# dmi.net
KiCad netlist of a schematic drawn in EAGLE
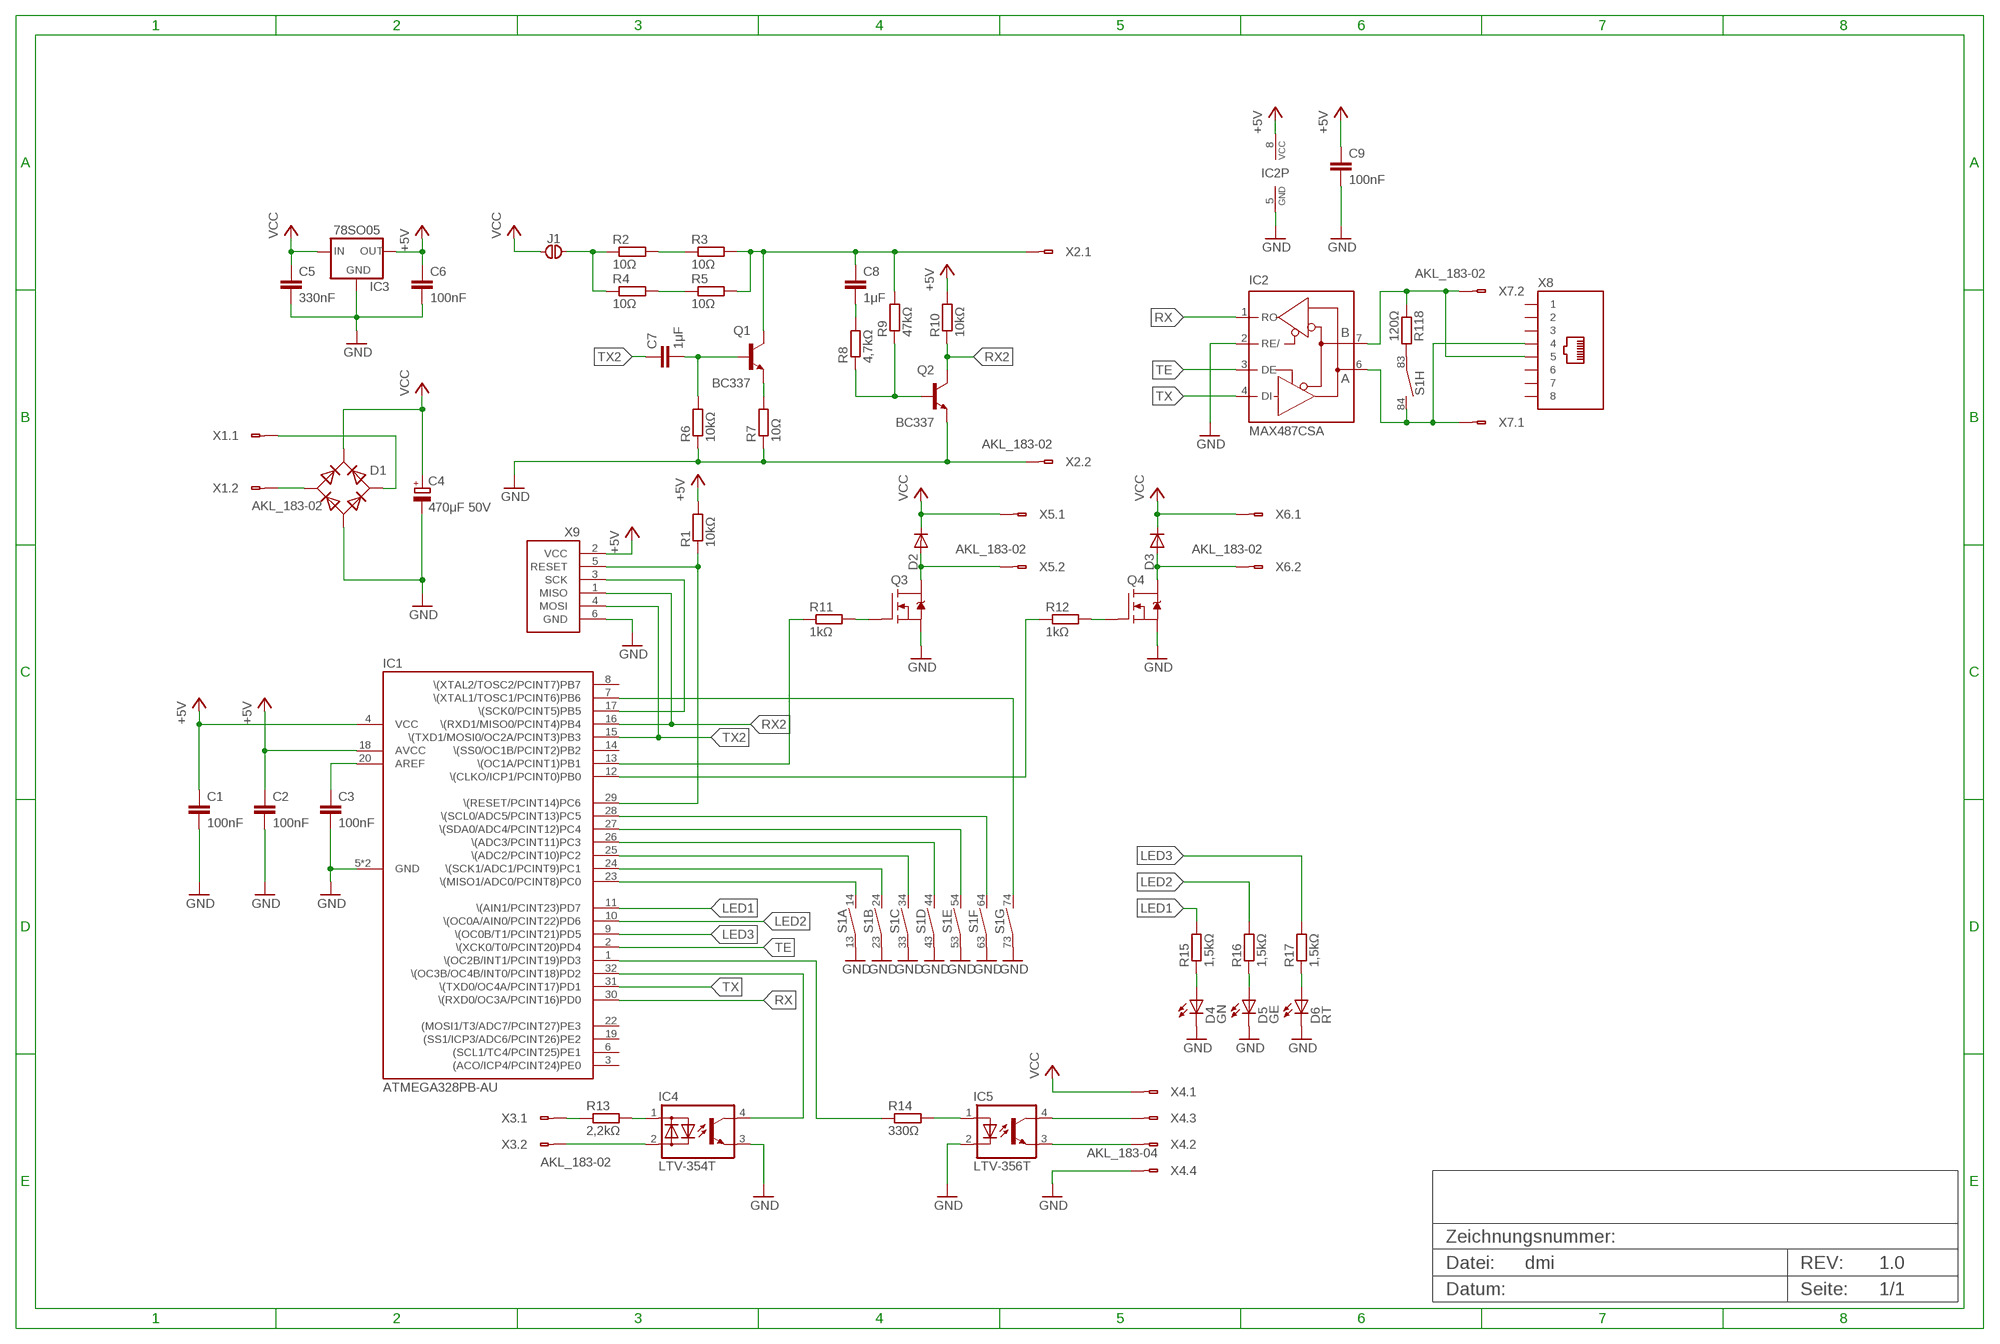
[diagram p0: schematic, sheet 1]

(export (version "E")
  (design (tool "Eeschema 10.0.6"))
  (components
    (comp (ref "C1")
      (value "100nF")
      (footprint "eagle-import:CHIP_0603")
      (libsource (lib "eagle-import") (part "C_0603"))
    )
    (comp (ref "C2")
      (value "100nF")
      (footprint "eagle-import:CHIP_0603")
      (libsource (lib "eagle-import") (part "C_0603"))
    )
    (comp (ref "C3")
      (value "100nF")
      (footprint "eagle-import:CHIP_0603")
      (libsource (lib "eagle-import") (part "C_0603"))
    )
    (comp (ref "C4")
      (value "470μF 50V")
      (footprint "eagle-import:E5-13")
      (libsource (lib "eagle-import") (part "C_EL_E5-13"))
    )
    (comp (ref "C5")
      (value "330nF")
      (footprint "eagle-import:CHIP_0805")
      (libsource (lib "eagle-import") (part "C_0805"))
    )
    (comp (ref "C6")
      (value "100nF")
      (footprint "eagle-import:CHIP_0805")
      (libsource (lib "eagle-import") (part "C_0805"))
    )
    (comp (ref "C7")
      (value "1μF")
      (footprint "eagle-import:CHIP_1206")
      (libsource (lib "eagle-import") (part "C_1206"))
    )
    (comp (ref "C8")
      (value "1μF")
      (footprint "eagle-import:CHIP_1206")
      (libsource (lib "eagle-import") (part "C_1206"))
    )
    (comp (ref "C9")
      (value "100nF")
      (footprint "eagle-import:CHIP_0603")
      (libsource (lib "eagle-import") (part "C_0603"))
    )
    (comp (ref "D1")
      (value "GLEICHRICHTER-SDIP")
      (footprint "eagle-import:SDIP04_508")
      (libsource (lib "eagle-import") (part "GLEICHRICHTER-SDIP"))
    )
    (comp (ref "D2")
      (value "DIODE-SOD123")
      (footprint "eagle-import:SOD123")
      (libsource (lib "eagle-import") (part "DIODE-SOD123"))
    )
    (comp (ref "D3")
      (value "DIODE-SOD123")
      (footprint "eagle-import:SOD123")
      (libsource (lib "eagle-import") (part "DIODE-SOD123"))
    )
    (comp (ref "D4")
      (value "GN")
      (footprint "eagle-import:CHIP_0805")
      (libsource (lib "eagle-import") (part "LED_0805"))
    )
    (comp (ref "D5")
      (value "GE")
      (footprint "eagle-import:CHIP_0805")
      (libsource (lib "eagle-import") (part "LED_0805"))
    )
    (comp (ref "D6")
      (value "RT")
      (footprint "eagle-import:CHIP_0805")
      (libsource (lib "eagle-import") (part "LED_0805"))
    )
    (comp (ref "IC1")
      (value "ATMEGA328PB-AU")
      (footprint "eagle-import:QFP32_08")
      (libsource (lib "eagle-import") (part "ATMEGA8PB-AU32"))
    )
    (comp (ref "IC2")
      (value "MAX487CSA")
      (footprint "eagle-import:SOP08_127")
      (libsource (lib "eagle-import") (part "MAX48CSA7"))
    )
    (comp (ref "IC3")
      (value "78SO05")
      (footprint "eagle-import:SOP08_127")
      (libsource (lib "eagle-import") (part "78?SO05"))
    )
    (comp (ref "IC4")
      (value "LTV-354T")
      (footprint "eagle-import:SOP04_254")
      (libsource (lib "eagle-import") (part "LTV-354T"))
    )
    (comp (ref "IC5")
      (value "LTV-356T")
      (footprint "eagle-import:SOP04_254")
      (libsource (lib "eagle-import") (part "LTV-356T"))
    )
    (comp (ref "J1")
      (value "JUMPER")
      (footprint "eagle-import:JUMPER2")
      (libsource (lib "eagle-import") (part "JUMPER"))
    )
    (comp (ref "Q1")
      (value "BC337")
      (footprint "eagle-import:SOT23")
      (libsource (lib "eagle-import") (part "NPN-SOT23-BEC"))
    )
    (comp (ref "Q2")
      (value "BC337")
      (footprint "eagle-import:SOT23")
      (libsource (lib "eagle-import") (part "NPN-SOT23-BEC"))
    )
    (comp (ref "Q3")
      (value "N-MOS-SOT23-GSD")
      (footprint "eagle-import:SOT23")
      (libsource (lib "eagle-import") (part "N-MOS-SOT23-GSD"))
    )
    (comp (ref "Q4")
      (value "N-MOS-SOT23-GSD")
      (footprint "eagle-import:SOT23")
      (libsource (lib "eagle-import") (part "N-MOS-SOT23-GSD"))
    )
    (comp (ref "R1")
      (value "10kΩ")
      (footprint "eagle-import:CHIP_0603")
      (libsource (lib "eagle-import") (part "R_0603"))
    )
    (comp (ref "R2")
      (value "10Ω")
      (footprint "eagle-import:CHIP_1206")
      (libsource (lib "eagle-import") (part "R_1206"))
    )
    (comp (ref "R3")
      (value "10Ω")
      (footprint "eagle-import:CHIP_1206")
      (libsource (lib "eagle-import") (part "R_1206"))
    )
    (comp (ref "R4")
      (value "10Ω")
      (footprint "eagle-import:CHIP_1206")
      (libsource (lib "eagle-import") (part "R_1206"))
    )
    (comp (ref "R5")
      (value "10Ω")
      (footprint "eagle-import:CHIP_1206")
      (libsource (lib "eagle-import") (part "R_1206"))
    )
    (comp (ref "R6")
      (value "10kΩ")
      (footprint "eagle-import:CHIP_0603")
      (libsource (lib "eagle-import") (part "R_0603"))
    )
    (comp (ref "R7")
      (value "10Ω")
      (footprint "eagle-import:CHIP_1206")
      (libsource (lib "eagle-import") (part "R_1206"))
    )
    (comp (ref "R8")
      (value "4,7kΩ")
      (footprint "eagle-import:CHIP_0603")
      (libsource (lib "eagle-import") (part "R_0603"))
    )
    (comp (ref "R9")
      (value "47kΩ")
      (footprint "eagle-import:CHIP_0603")
      (libsource (lib "eagle-import") (part "R_0603"))
    )
    (comp (ref "R10")
      (value "10kΩ")
      (footprint "eagle-import:CHIP_0603")
      (libsource (lib "eagle-import") (part "R_0603"))
    )
    (comp (ref "R11")
      (value "1kΩ")
      (footprint "eagle-import:CHIP_0603")
      (libsource (lib "eagle-import") (part "R_0603"))
    )
    (comp (ref "R12")
      (value "1kΩ")
      (footprint "eagle-import:CHIP_0603")
      (libsource (lib "eagle-import") (part "R_0603"))
    )
    (comp (ref "R13")
      (value "2,2kΩ")
      (footprint "eagle-import:CHIP_0603")
      (libsource (lib "eagle-import") (part "R_0603"))
    )
    (comp (ref "R14")
      (value "330Ω")
      (footprint "eagle-import:CHIP_0603")
      (libsource (lib "eagle-import") (part "R_0603"))
    )
    (comp (ref "R15")
      (value "1,5kΩ")
      (footprint "eagle-import:CHIP_0603")
      (libsource (lib "eagle-import") (part "R_0603"))
    )
    (comp (ref "R16")
      (value "1,5kΩ")
      (footprint "eagle-import:CHIP_0603")
      (libsource (lib "eagle-import") (part "R_0603"))
    )
    (comp (ref "R17")
      (value "1,5kΩ")
      (footprint "eagle-import:CHIP_0603")
      (libsource (lib "eagle-import") (part "R_0603"))
    )
    (comp (ref "R118")
      (value "120Ω")
      (footprint "eagle-import:CHIP_0805")
      (libsource (lib "eagle-import") (part "R_0805"))
    )
    (comp (ref "S1")
      (value "DP08D")
      (footprint "eagle-import:DIP08_SMD")
      (libsource (lib "eagle-import") (part "DP08D"))
    )
    (comp (ref "X1")
      (value "AKL_183-02")
      (footprint "eagle-import:AKL_183-02")
      (libsource (lib "eagle-import") (part "AKL_183-02"))
    )
    (comp (ref "X2")
      (value "AKL_183-02")
      (footprint "eagle-import:AKL_183-02")
      (libsource (lib "eagle-import") (part "AKL_183-02"))
    )
    (comp (ref "X3")
      (value "AKL_183-02")
      (footprint "eagle-import:AKL_183-02")
      (libsource (lib "eagle-import") (part "AKL_183-02"))
    )
    (comp (ref "X4")
      (value "AKL_183-04")
      (footprint "eagle-import:AKL_183-04")
      (libsource (lib "eagle-import") (part "AKL_183-04"))
    )
    (comp (ref "X5")
      (value "AKL_183-02")
      (footprint "eagle-import:AKL_183-02")
      (libsource (lib "eagle-import") (part "AKL_183-02"))
    )
    (comp (ref "X6")
      (value "AKL_183-02")
      (footprint "eagle-import:AKL_183-02")
      (libsource (lib "eagle-import") (part "AKL_183-02"))
    )
    (comp (ref "X7")
      (value "AKL_183-02")
      (footprint "eagle-import:AKL_183-02")
      (libsource (lib "eagle-import") (part "AKL_183-02"))
    )
    (comp (ref "X8")
      (value "8P8C")
      (footprint "eagle-import:C-BMJ-0102")
      (libsource (lib "eagle-import") (part "8P8C"))
    )
    (comp (ref "X9")
      (value "ISP-AVR6")
      (footprint "eagle-import:ML6")
      (libsource (lib "eagle-import") (part "ISP-AVR6"))
    )
  )
  (nets
    (net (code "1") (name "+5V") (class "Default")
      (node (ref "C1") (pin "1") (pinfunction "1_1") (pintype "passive"))
      (node (ref "C2") (pin "1") (pinfunction "1_1") (pintype "passive"))
      (node (ref "C6") (pin "1") (pinfunction "1_1") (pintype "passive"))
      (node (ref "C9") (pin "1") (pinfunction "1_1") (pintype "passive"))
      (node (ref "IC1") (pin "18") (pinfunction "AVCC_18") (pintype "power_in"))
      (node (ref "IC1") (pin "4") (pinfunction "VCC_4") (pintype "power_in"))
      (node (ref "IC2") (pin "8") (pinfunction "VCC_8") (pintype "power_in"))
      (node (ref "IC3") (pin "1") (pinfunction "OUT_1") (pintype "passive"))
      (node (ref "R1") (pin "2") (pinfunction "2_2") (pintype "passive"))
      (node (ref "R10") (pin "2") (pinfunction "2_2") (pintype "passive"))
      (node (ref "X9") (pin "2") (pinfunction "VCC_2") (pintype "power_in"))
    )
    (net (code "2") (name "GND") (class "Default")
      (node (ref "C1") (pin "2") (pinfunction "2_2") (pintype "passive"))
      (node (ref "C2") (pin "2") (pinfunction "2_2") (pintype "passive"))
      (node (ref "C3") (pin "2") (pinfunction "2_2") (pintype "passive"))
      (node (ref "C4") (pin "-") (pinfunction "-_-") (pintype "passive"))
      (node (ref "C5") (pin "2") (pinfunction "2_2") (pintype "passive"))
      (node (ref "C6") (pin "2") (pinfunction "2_2") (pintype "passive"))
      (node (ref "C9") (pin "2") (pinfunction "2_2") (pintype "passive"))
      (node (ref "D1") (pin "2") (pinfunction "-_2") (pintype "passive"))
      (node (ref "D4") (pin "2") (pinfunction "C_2") (pintype "passive"))
      (node (ref "D5") (pin "2") (pinfunction "C_2") (pintype "passive"))
      (node (ref "D6") (pin "2") (pinfunction "C_2") (pintype "passive"))
      (node (ref "IC1") (pin "21") (pinfunction "GND_21") (pintype "power_in"))
      (node (ref "IC1") (pin "5") (pinfunction "GND_5") (pintype "power_in"))
      (node (ref "IC2") (pin "2") (pinfunction "RE/_2") (pintype "input"))
      (node (ref "IC2") (pin "5") (pinfunction "GND_5") (pintype "power_in"))
      (node (ref "IC3") (pin "2") (pinfunction "GND_2") (pintype "input"))
      (node (ref "IC3") (pin "3") (pinfunction "GND_3") (pintype "input"))
      (node (ref "IC3") (pin "6") (pinfunction "GND_6") (pintype "input"))
      (node (ref "IC3") (pin "7") (pinfunction "GND_7") (pintype "input"))
      (node (ref "IC4") (pin "3") (pinfunction "E_3") (pintype "passive"))
      (node (ref "IC5") (pin "2") (pinfunction "K_2") (pintype "passive"))
      (node (ref "Q2") (pin "2") (pinfunction "E_2") (pintype "passive"))
      (node (ref "Q3") (pin "2") (pinfunction "S_2") (pintype "passive"))
      (node (ref "Q4") (pin "2") (pinfunction "S_2") (pintype "passive"))
      (node (ref "R6") (pin "1") (pinfunction "1_1") (pintype "passive"))
      (node (ref "R7") (pin "1") (pinfunction "1_1") (pintype "passive"))
      (node (ref "S1") (pin "13") (pinfunction "3_13") (pintype "passive"))
      (node (ref "S1") (pin "23") (pinfunction "3_23") (pintype "passive"))
      (node (ref "S1") (pin "33") (pinfunction "3_33") (pintype "passive"))
      (node (ref "S1") (pin "43") (pinfunction "3_43") (pintype "passive"))
      (node (ref "S1") (pin "53") (pinfunction "3_53") (pintype "passive"))
      (node (ref "S1") (pin "63") (pinfunction "3_63") (pintype "passive"))
      (node (ref "S1") (pin "73") (pinfunction "3_73") (pintype "passive"))
      (node (ref "X2") (pin "2") (pinfunction "A_2") (pintype "passive"))
      (node (ref "X4") (pin "4") (pinfunction "A_4") (pintype "passive"))
      (node (ref "X9") (pin "6") (pinfunction "GND_6") (pintype "power_in"))
    )
    (net (code "3") (name "LED1") (class "Default")
      (node (ref "IC1") (pin "11") (pinfunction "\\(AIN1/PCINT23)PD7_11") (pintype "bidirectional"))
      (node (ref "R15") (pin "2") (pinfunction "2_2") (pintype "passive"))
    )
    (net (code "4") (name "LED2") (class "Default")
      (node (ref "IC1") (pin "10") (pinfunction "\\(OC0A/AIN0/PCINT22)PD6_10") (pintype "bidirectional"))
      (node (ref "R16") (pin "2") (pinfunction "2_2") (pintype "passive"))
    )
    (net (code "5") (name "LED3") (class "Default")
      (node (ref "IC1") (pin "9") (pinfunction "\\(OC0B/T1/PCINT21)PD5_9") (pintype "bidirectional"))
      (node (ref "R17") (pin "2") (pinfunction "2_2") (pintype "passive"))
    )
    (net (code "6") (name "Net-(C8-Pad2)") (class "Default")
      (node (ref "C8") (pin "2") (pinfunction "2_2") (pintype "passive"))
      (node (ref "R8") (pin "2") (pinfunction "2_2") (pintype "passive"))
    )
    (net (code "7") (name "Net-(D1-AC1)") (class "Default")
      (node (ref "D1") (pin "3") (pinfunction "AC1_3") (pintype "passive"))
      (node (ref "X1") (pin "2") (pinfunction "A_2") (pintype "passive"))
    )
    (net (code "8") (name "Net-(D1-AC2)") (class "Default")
      (node (ref "D1") (pin "4") (pinfunction "AC2_4") (pintype "passive"))
      (node (ref "X1") (pin "1") (pinfunction "A_1") (pintype "passive"))
    )
    (net (code "9") (name "Net-(D4-A)") (class "Default")
      (node (ref "D4") (pin "1") (pinfunction "A_1") (pintype "passive"))
      (node (ref "R15") (pin "1") (pinfunction "1_1") (pintype "passive"))
    )
    (net (code "10") (name "Net-(D5-A)") (class "Default")
      (node (ref "D5") (pin "1") (pinfunction "A_1") (pintype "passive"))
      (node (ref "R16") (pin "1") (pinfunction "1_1") (pintype "passive"))
    )
    (net (code "11") (name "Net-(D6-A)") (class "Default")
      (node (ref "D6") (pin "1") (pinfunction "A_1") (pintype "passive"))
      (node (ref "R17") (pin "1") (pinfunction "1_1") (pintype "passive"))
    )
    (net (code "12") (name "Net-(IC1-AREF)") (class "Default")
      (node (ref "C3") (pin "1") (pinfunction "1_1") (pintype "passive"))
      (node (ref "IC1") (pin "20") (pinfunction "AREF_20") (pintype "passive"))
    )
    (net (code "13") (name "Net-(IC1-\\(ADC2{slash}PCINT10)PC2)") (class "Default")
      (node (ref "IC1") (pin "25") (pinfunction "\\(ADC2/PCINT10)PC2_25") (pintype "bidirectional"))
      (node (ref "S1") (pin "34") (pinfunction "4_34") (pintype "passive"))
    )
    (net (code "14") (name "Net-(IC1-\\(ADC3{slash}PCINT11)PC3)") (class "Default")
      (node (ref "IC1") (pin "26") (pinfunction "\\(ADC3/PCINT11)PC3_26") (pintype "bidirectional"))
      (node (ref "S1") (pin "44") (pinfunction "4_44") (pintype "passive"))
    )
    (net (code "15") (name "Net-(IC1-\\(CLKO{slash}ICP1{slash}PCINT0)PB0)") (class "Default")
      (node (ref "IC1") (pin "12") (pinfunction "\\(CLKO/ICP1/PCINT0)PB0_12") (pintype "bidirectional"))
      (node (ref "R12") (pin "1") (pinfunction "1_1") (pintype "passive"))
    )
    (net (code "16") (name "Net-(IC1-\\(MISO1{slash}ADC0{slash}PCINT8)PC0)") (class "Default")
      (node (ref "IC1") (pin "23") (pinfunction "\\(MISO1/ADC0/PCINT8)PC0_23") (pintype "bidirectional"))
      (node (ref "S1") (pin "14") (pinfunction "4_14") (pintype "passive"))
    )
    (net (code "17") (name "Net-(IC1-\\(OC1A{slash}PCINT1)PB1)") (class "Default")
      (node (ref "IC1") (pin "13") (pinfunction "\\(OC1A/PCINT1)PB1_13") (pintype "bidirectional"))
      (node (ref "R11") (pin "1") (pinfunction "1_1") (pintype "passive"))
    )
    (net (code "18") (name "Net-(IC1-\\(OC2B{slash}INT1{slash}PCINT19)PD3)") (class "Default")
      (node (ref "IC1") (pin "1") (pinfunction "\\(OC2B/INT1/PCINT19)PD3_1") (pintype "bidirectional"))
      (node (ref "R14") (pin "1") (pinfunction "1_1") (pintype "passive"))
    )
    (net (code "19") (name "Net-(IC1-\\(OC3B{slash}OC4B{slash}INT0{slash}PCINT18)PD2)") (class "Default")
      (node (ref "IC1") (pin "32") (pinfunction "\\(OC3B/OC4B/INT0/PCINT18)PD2_32") (pintype "bidirectional"))
      (node (ref "IC4") (pin "4") (pinfunction "C_4") (pintype "passive"))
    )
    (net (code "20") (name "Net-(IC1-\\(RESET{slash}PCINT14)PC6)") (class "Default")
      (node (ref "IC1") (pin "29") (pinfunction "\\(RESET/PCINT14)PC6_29") (pintype "bidirectional"))
      (node (ref "R1") (pin "1") (pinfunction "1_1") (pintype "passive"))
      (node (ref "X9") (pin "5") (pinfunction "RESET_5") (pintype "passive"))
    )
    (net (code "21") (name "Net-(IC1-\\(SCK0{slash}PCINT5)PB5)") (class "Default")
      (node (ref "IC1") (pin "17") (pinfunction "\\(SCK0/PCINT5)PB5_17") (pintype "bidirectional"))
      (node (ref "X9") (pin "3") (pinfunction "SCK_3") (pintype "passive"))
    )
    (net (code "22") (name "Net-(IC1-\\(SCK1{slash}ADC1{slash}PCINT9)PC1)") (class "Default")
      (node (ref "IC1") (pin "24") (pinfunction "\\(SCK1/ADC1/PCINT9)PC1_24") (pintype "bidirectional"))
      (node (ref "S1") (pin "24") (pinfunction "4_24") (pintype "passive"))
    )
    (net (code "23") (name "Net-(IC1-\\(SCL0{slash}ADC5{slash}PCINT13)PC5)") (class "Default")
      (node (ref "IC1") (pin "28") (pinfunction "\\(SCL0/ADC5/PCINT13)PC5_28") (pintype "bidirectional"))
      (node (ref "S1") (pin "64") (pinfunction "4_64") (pintype "passive"))
    )
    (net (code "24") (name "Net-(IC1-\\(SDA0{slash}ADC4{slash}PCINT12)PC4)") (class "Default")
      (node (ref "IC1") (pin "27") (pinfunction "\\(SDA0/ADC4/PCINT12)PC4_27") (pintype "bidirectional"))
      (node (ref "S1") (pin "54") (pinfunction "4_54") (pintype "passive"))
    )
    (net (code "25") (name "Net-(IC1-\\(XTAL1{slash}TOSC1{slash}PCINT6)PB6)") (class "Default")
      (node (ref "IC1") (pin "7") (pinfunction "\\(XTAL1/TOSC1/PCINT6)PB6_7") (pintype "bidirectional"))
      (node (ref "S1") (pin "74") (pinfunction "4_74") (pintype "passive"))
    )
    (net (code "26") (name "Net-(IC2A-A)") (class "Default")
      (node (ref "IC2") (pin "6") (pinfunction "A_6") (pintype "passive"))
      (node (ref "S1") (pin "84") (pinfunction "4_84") (pintype "passive"))
      (node (ref "X7") (pin "1") (pinfunction "A_1") (pintype "passive"))
      (node (ref "X8") (pin "P$4") (pinfunction "4_P$4") (pintype "passive"))
    )
    (net (code "27") (name "Net-(IC2A-B)") (class "Default")
      (node (ref "IC2") (pin "7") (pinfunction "B_7") (pintype "passive"))
      (node (ref "R118") (pin "1") (pinfunction "1_1") (pintype "passive"))
      (node (ref "X7") (pin "2") (pinfunction "A_2") (pintype "passive"))
      (node (ref "X8") (pin "P$5") (pinfunction "5_P$5") (pintype "passive"))
    )
    (net (code "28") (name "Net-(IC4-A)") (class "Default")
      (node (ref "IC4") (pin "1") (pinfunction "A_1") (pintype "passive"))
      (node (ref "R13") (pin "2") (pinfunction "2_2") (pintype "passive"))
    )
    (net (code "29") (name "Net-(IC4-K)") (class "Default")
      (node (ref "IC4") (pin "2") (pinfunction "K_2") (pintype "passive"))
      (node (ref "X3") (pin "2") (pinfunction "A_2") (pintype "passive"))
    )
    (net (code "30") (name "Net-(IC5-A)") (class "Default")
      (node (ref "IC5") (pin "1") (pinfunction "A_1") (pintype "passive"))
      (node (ref "R14") (pin "2") (pinfunction "2_2") (pintype "passive"))
    )
    (net (code "31") (name "Net-(IC5-C)") (class "Default")
      (node (ref "IC5") (pin "4") (pinfunction "C_4") (pintype "passive"))
      (node (ref "X4") (pin "3") (pinfunction "A_3") (pintype "passive"))
    )
    (net (code "32") (name "Net-(IC5-E)") (class "Default")
      (node (ref "IC5") (pin "3") (pinfunction "E_3") (pintype "passive"))
      (node (ref "X4") (pin "2") (pinfunction "A_2") (pintype "passive"))
    )
    (net (code "33") (name "Net-(J1-PadP$2)") (class "Default")
      (node (ref "J1") (pin "P$2") (pinfunction "P$2_P$2") (pintype "passive"))
      (node (ref "R2") (pin "1") (pinfunction "1_1") (pintype "passive"))
      (node (ref "R4") (pin "1") (pinfunction "1_1") (pintype "passive"))
    )
    (net (code "34") (name "Net-(Q1-B)") (class "Default")
      (node (ref "C7") (pin "2") (pinfunction "2_2") (pintype "passive"))
      (node (ref "Q1") (pin "1") (pinfunction "B_1") (pintype "passive"))
      (node (ref "R6") (pin "2") (pinfunction "2_2") (pintype "passive"))
    )
    (net (code "35") (name "Net-(Q1-C)") (class "Default")
      (node (ref "C8") (pin "1") (pinfunction "1_1") (pintype "passive"))
      (node (ref "Q1") (pin "3") (pinfunction "C_3") (pintype "passive"))
      (node (ref "R3") (pin "2") (pinfunction "2_2") (pintype "passive"))
      (node (ref "R5") (pin "2") (pinfunction "2_2") (pintype "passive"))
      (node (ref "R9") (pin "2") (pinfunction "2_2") (pintype "passive"))
      (node (ref "X2") (pin "1") (pinfunction "A_1") (pintype "passive"))
    )
    (net (code "36") (name "Net-(Q1-E)") (class "Default")
      (node (ref "Q1") (pin "2") (pinfunction "E_2") (pintype "passive"))
      (node (ref "R7") (pin "2") (pinfunction "2_2") (pintype "passive"))
    )
    (net (code "37") (name "Net-(Q2-B)") (class "Default")
      (node (ref "Q2") (pin "1") (pinfunction "B_1") (pintype "passive"))
      (node (ref "R8") (pin "1") (pinfunction "1_1") (pintype "passive"))
      (node (ref "R9") (pin "1") (pinfunction "1_1") (pintype "passive"))
    )
    (net (code "38") (name "Net-(Q3-D)") (class "Default")
      (node (ref "D2") (pin "A") (pinfunction "A_A") (pintype "passive"))
      (node (ref "Q3") (pin "3") (pinfunction "D_3") (pintype "passive"))
      (node (ref "X5") (pin "2") (pinfunction "A_2") (pintype "passive"))
    )
    (net (code "39") (name "Net-(Q3-G)") (class "Default")
      (node (ref "Q3") (pin "1") (pinfunction "G_1") (pintype "passive"))
      (node (ref "R11") (pin "2") (pinfunction "2_2") (pintype "passive"))
    )
    (net (code "40") (name "Net-(Q4-D)") (class "Default")
      (node (ref "D3") (pin "A") (pinfunction "A_A") (pintype "passive"))
      (node (ref "Q4") (pin "3") (pinfunction "D_3") (pintype "passive"))
      (node (ref "X6") (pin "2") (pinfunction "A_2") (pintype "passive"))
    )
    (net (code "41") (name "Net-(Q4-G)") (class "Default")
      (node (ref "Q4") (pin "1") (pinfunction "G_1") (pintype "passive"))
      (node (ref "R12") (pin "2") (pinfunction "2_2") (pintype "passive"))
    )
    (net (code "42") (name "Net-(R2-Pad2)") (class "Default")
      (node (ref "R2") (pin "2") (pinfunction "2_2") (pintype "passive"))
      (node (ref "R3") (pin "1") (pinfunction "1_1") (pintype "passive"))
    )
    (net (code "43") (name "Net-(R4-Pad2)") (class "Default")
      (node (ref "R4") (pin "2") (pinfunction "2_2") (pintype "passive"))
      (node (ref "R5") (pin "1") (pinfunction "1_1") (pintype "passive"))
    )
    (net (code "44") (name "Net-(S1H-3)") (class "Default")
      (node (ref "R118") (pin "2") (pinfunction "2_2") (pintype "passive"))
      (node (ref "S1") (pin "83") (pinfunction "3_83") (pintype "passive"))
    )
    (net (code "45") (name "Net-(X3A-A)") (class "Default")
      (node (ref "R13") (pin "1") (pinfunction "1_1") (pintype "passive"))
      (node (ref "X3") (pin "1") (pinfunction "A_1") (pintype "passive"))
    )
    (net (code "46") (name "RX") (class "Default")
      (node (ref "IC1") (pin "30") (pinfunction "\\(RXD0/OC3A/PCINT16)PD0_30") (pintype "bidirectional"))
      (node (ref "IC2") (pin "1") (pinfunction "RO_1") (pintype "output"))
    )
    (net (code "47") (name "RX2") (class "Default")
      (node (ref "IC1") (pin "16") (pinfunction "\\(RXD1/MISO0/PCINT4)PB4_16") (pintype "bidirectional"))
      (node (ref "Q2") (pin "3") (pinfunction "C_3") (pintype "passive"))
      (node (ref "R10") (pin "1") (pinfunction "1_1") (pintype "passive"))
      (node (ref "X9") (pin "1") (pinfunction "MISO_1") (pintype "passive"))
    )
    (net (code "48") (name "TE") (class "Default")
      (node (ref "IC1") (pin "2") (pinfunction "\\(XCK0/T0/PCINT20)PD4_2") (pintype "bidirectional"))
      (node (ref "IC2") (pin "3") (pinfunction "DE_3") (pintype "input"))
    )
    (net (code "49") (name "TX") (class "Default")
      (node (ref "IC1") (pin "31") (pinfunction "\\(TXD0/OC4A/PCINT17)PD1_31") (pintype "bidirectional"))
      (node (ref "IC2") (pin "4") (pinfunction "DI_4") (pintype "input"))
    )
    (net (code "50") (name "TX2") (class "Default")
      (node (ref "C7") (pin "1") (pinfunction "1_1") (pintype "passive"))
      (node (ref "IC1") (pin "15") (pinfunction "\\(TXD1/MOSI0/OC2A/PCINT3)PB3_15") (pintype "bidirectional"))
      (node (ref "X9") (pin "4") (pinfunction "MOSI_4") (pintype "passive"))
    )
    (net (code "51") (name "VCC") (class "Default")
      (node (ref "C4") (pin "+") (pinfunction "+_+") (pintype "passive"))
      (node (ref "C5") (pin "1") (pinfunction "1_1") (pintype "passive"))
      (node (ref "D1") (pin "1") (pinfunction "+_1") (pintype "passive"))
      (node (ref "D2") (pin "K") (pinfunction "K_K") (pintype "passive"))
      (node (ref "D3") (pin "K") (pinfunction "K_K") (pintype "passive"))
      (node (ref "IC3") (pin "8") (pinfunction "IN_8") (pintype "input"))
      (node (ref "J1") (pin "P$1") (pinfunction "P$1_P$1") (pintype "passive"))
      (node (ref "X4") (pin "1") (pinfunction "A_1") (pintype "passive"))
      (node (ref "X5") (pin "1") (pinfunction "A_1") (pintype "passive"))
      (node (ref "X6") (pin "1") (pinfunction "A_1") (pintype "passive"))
    )
    (net (code "52") (name "unconnected-(IC1-(ACO{slash}ICP4{slash}PCINT24)PE0-Pad3)") (class "Default")
      (node (ref "IC1") (pin "3") (pinfunction "(ACO/ICP4/PCINT24)PE0_3") (pintype "bidirectional"))
    )
    (net (code "53") (name "unconnected-(IC1-(MOSI1{slash}T3{slash}ADC7{slash}PCINT27)PE3-Pad22)") (class "Default")
      (node (ref "IC1") (pin "22") (pinfunction "(MOSI1/T3/ADC7/PCINT27)PE3_22") (pintype "bidirectional"))
    )
    (net (code "54") (name "unconnected-(IC1-(SCL1{slash}TC4{slash}PCINT25)PE1-Pad6)") (class "Default")
      (node (ref "IC1") (pin "6") (pinfunction "(SCL1/TC4/PCINT25)PE1_6") (pintype "bidirectional"))
    )
    (net (code "55") (name "unconnected-(IC1-(SS1{slash}ICP3{slash}ADC6{slash}PCINT26)PE2-Pad19)") (class "Default")
      (node (ref "IC1") (pin "19") (pinfunction "(SS1/ICP3/ADC6/PCINT26)PE2_19") (pintype "bidirectional"))
    )
    (net (code "56") (name "unconnected-(IC1-\\(SS0{slash}OC1B{slash}PCINT2)PB2-Pad14)") (class "Default")
      (node (ref "IC1") (pin "14") (pinfunction "\\(SS0/OC1B/PCINT2)PB2_14") (pintype "bidirectional"))
    )
    (net (code "57") (name "unconnected-(IC1-\\(XTAL2{slash}TOSC2{slash}PCINT7)PB7-Pad8)") (class "Default")
      (node (ref "IC1") (pin "8") (pinfunction "\\(XTAL2/TOSC2/PCINT7)PB7_8") (pintype "bidirectional"))
    )
    (net (code "58") (name "unconnected-(X8-1-PadP$1)") (class "Default")
      (node (ref "X8") (pin "P$1") (pinfunction "1_P$1") (pintype "passive"))
    )
    (net (code "59") (name "unconnected-(X8-2-PadP$2)") (class "Default")
      (node (ref "X8") (pin "P$2") (pinfunction "2_P$2") (pintype "passive"))
    )
    (net (code "60") (name "unconnected-(X8-3-PadP$3)") (class "Default")
      (node (ref "X8") (pin "P$3") (pinfunction "3_P$3") (pintype "passive"))
    )
    (net (code "61") (name "unconnected-(X8-6-PadP$6)") (class "Default")
      (node (ref "X8") (pin "P$6") (pinfunction "6_P$6") (pintype "passive"))
    )
    (net (code "62") (name "unconnected-(X8-7-PadP$7)") (class "Default")
      (node (ref "X8") (pin "P$7") (pinfunction "7_P$7") (pintype "passive"))
    )
    (net (code "63") (name "unconnected-(X8-8-PadP$8)") (class "Default")
      (node (ref "X8") (pin "P$8") (pinfunction "8_P$8") (pintype "passive"))
    )
  )
)
